# my-hello-world.net
KiCad netlist of a schematic drawn in EAGLE
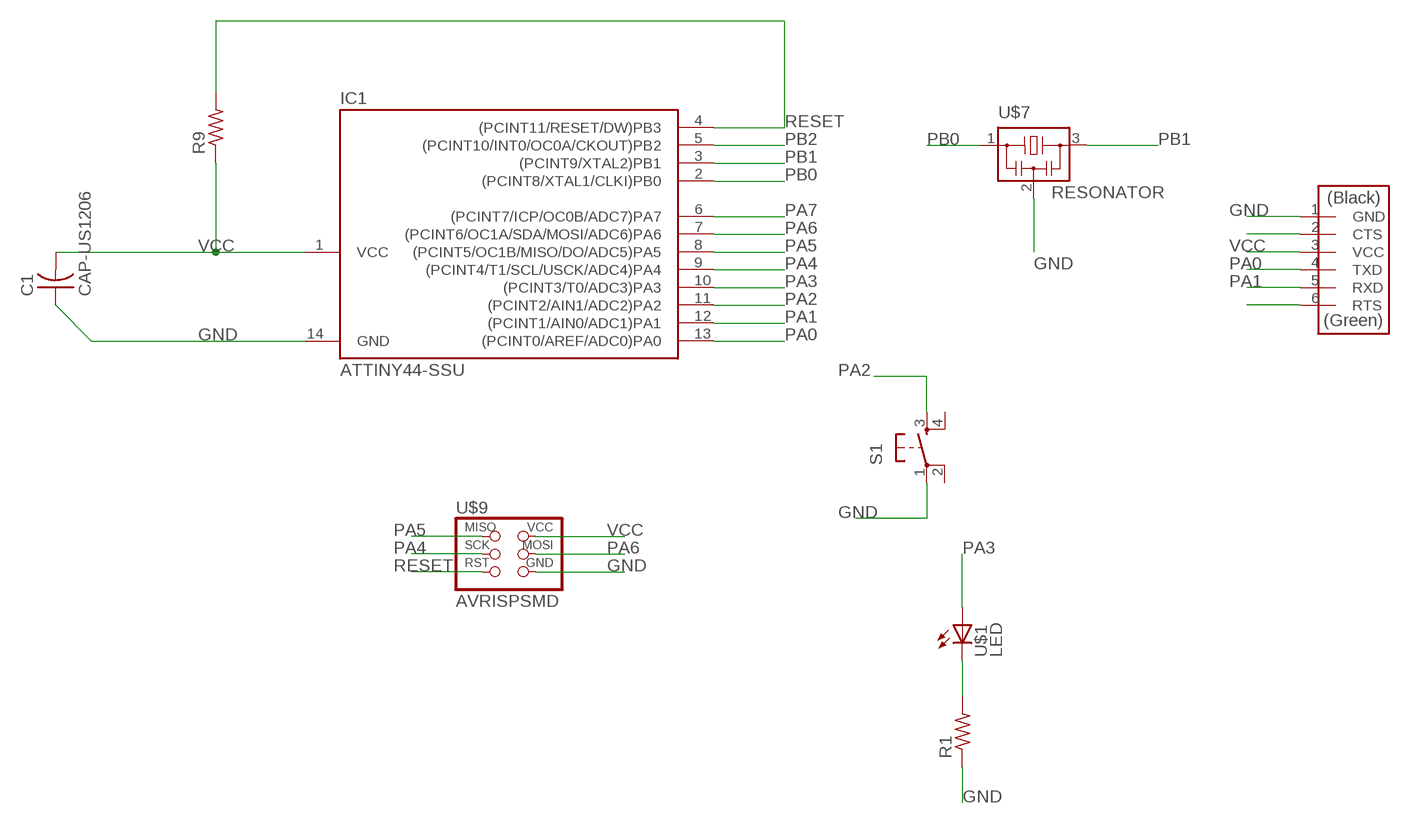
[diagram p0: schematic, sheet 1]

(export (version "E")
  (design (tool "Eeschema 10.0.6"))
  (components
    (comp (ref "C1")
      (value "CAP-US1206")
      (footprint "eagle-import:C1206")
      (libsource (lib "eagle-import") (part "CAP-US1206"))
    )
    (comp (ref "IC1")
      (value "ATTINY44-SSU")
      (footprint "eagle-import:SOIC14")
      (libsource (lib "eagle-import") (part "ATTINY44-SSU"))
    )
    (comp (ref "R1")
      (value "RES-US1206")
      (footprint "eagle-import:R1206")
      (libsource (lib "eagle-import") (part "RES-US1206"))
    )
    (comp (ref "R9")
      (value "RES-US1206")
      (footprint "eagle-import:R1206")
      (libsource (lib "eagle-import") (part "RES-US1206"))
    )
    (comp (ref "S1")
      (value "6MM_SWITCH6MM_SWITCH")
      (footprint "eagle-import:6MM_SWITCH")
      (libsource (lib "eagle-import") (part "6MM_SWITCH6MM_SWITCH"))
    )
    (comp (ref "U$1")
      (value "LED")
      (footprint "eagle-import:LED1206")
      (libsource (lib "eagle-import") (part "LED"))
    )
    (comp (ref "U$7")
      (value "RESONATOR")
      (footprint "eagle-import:EFOBM")
      (libsource (lib "eagle-import") (part "RESONATOR"))
    )
    (comp (ref "U$9")
      (value "AVRISPSMD")
      (footprint "eagle-import:2X03SMD")
      (libsource (lib "eagle-import") (part "AVRISPSMD"))
    )
    (comp (ref "U$10")
      (value "FTDI-SMD-HEADER")
      (footprint "eagle-import:1X06SMD")
      (libsource (lib "eagle-import") (part "FTDI-SMD-HEADER"))
    )
  )
  (nets
    (net (code "1") (name "/GND") (class "Default")
      (node (ref "C1") (pin "1") (pinfunction "1_1") (pintype "passive"))
      (node (ref "IC1") (pin "14") (pinfunction "GND_14") (pintype "power_in"))
      (node (ref "R1") (pin "1") (pinfunction "1_1") (pintype "passive"))
      (node (ref "S1") (pin "1") (pinfunction "P_1") (pintype "passive"))
      (node (ref "U$10") (pin "1") (pinfunction "GND_1") (pintype "bidirectional"))
      (node (ref "U$7") (pin "2") (pinfunction "2_2") (pintype "passive"))
      (node (ref "U$9") (pin "6") (pinfunction "GND_6") (pintype "passive"))
    )
    (net (code "2") (name "/PA0") (class "Default")
      (node (ref "IC1") (pin "13") (pinfunction "(PCINT0/AREF/ADC0)PA0_13") (pintype "bidirectional"))
      (node (ref "U$10") (pin "4") (pinfunction "TXD_4") (pintype "bidirectional"))
    )
    (net (code "3") (name "/PA1") (class "Default")
      (node (ref "IC1") (pin "12") (pinfunction "(PCINT1/AIN0/ADC1)PA1_12") (pintype "bidirectional"))
      (node (ref "U$10") (pin "5") (pinfunction "RXD_5") (pintype "bidirectional"))
    )
    (net (code "4") (name "/PA2") (class "Default")
      (node (ref "IC1") (pin "11") (pinfunction "(PCINT2/AIN1/ADC2)PA2_11") (pintype "bidirectional"))
      (node (ref "S1") (pin "3") (pinfunction "S_3") (pintype "passive"))
    )
    (net (code "5") (name "/PA3") (class "Default")
      (node (ref "IC1") (pin "10") (pinfunction "(PCINT3/T0/ADC3)PA3_10") (pintype "bidirectional"))
      (node (ref "U$1") (pin "1") (pinfunction "A_1") (pintype "passive"))
    )
    (net (code "6") (name "/PA4") (class "Default")
      (node (ref "IC1") (pin "9") (pinfunction "(PCINT4/T1/SCL/USCK/ADC4)PA4_9") (pintype "bidirectional"))
      (node (ref "U$9") (pin "3") (pinfunction "SCK_3") (pintype "passive"))
    )
    (net (code "7") (name "/PA5") (class "Default")
      (node (ref "IC1") (pin "8") (pinfunction "(PCINT5/OC1B/MISO/DO/ADC5)PA5_8") (pintype "bidirectional"))
      (node (ref "U$9") (pin "1") (pinfunction "MISO_1") (pintype "passive"))
    )
    (net (code "8") (name "/PA6") (class "Default")
      (node (ref "IC1") (pin "7") (pinfunction "(PCINT6/OC1A/SDA/MOSI/ADC6)PA6_7") (pintype "bidirectional"))
      (node (ref "U$9") (pin "4") (pinfunction "MOSI_4") (pintype "passive"))
    )
    (net (code "9") (name "/PA7") (class "Default")
      (node (ref "IC1") (pin "6") (pinfunction "(PCINT7/ICP/OC0B/ADC7)PA7_6") (pintype "bidirectional"))
    )
    (net (code "10") (name "/PB0") (class "Default")
      (node (ref "IC1") (pin "2") (pinfunction "(PCINT8/XTAL1/CLKI)PB0_2") (pintype "bidirectional"))
      (node (ref "U$7") (pin "1") (pinfunction "1_1") (pintype "passive"))
    )
    (net (code "11") (name "/PB1") (class "Default")
      (node (ref "IC1") (pin "3") (pinfunction "(PCINT9/XTAL2)PB1_3") (pintype "bidirectional"))
      (node (ref "U$7") (pin "3") (pinfunction "3_3") (pintype "passive"))
    )
    (net (code "12") (name "/PB2") (class "Default")
      (node (ref "IC1") (pin "5") (pinfunction "(PCINT10/INT0/OC0A/CKOUT)PB2_5") (pintype "bidirectional"))
    )
    (net (code "13") (name "/RESET") (class "Default")
      (node (ref "IC1") (pin "4") (pinfunction "(PCINT11/RESET/DW)PB3_4") (pintype "bidirectional"))
      (node (ref "R9") (pin "2") (pinfunction "2_2") (pintype "passive"))
      (node (ref "U$9") (pin "5") (pinfunction "RST_5") (pintype "passive"))
    )
    (net (code "14") (name "/VCC") (class "Default")
      (node (ref "C1") (pin "2") (pinfunction "2_2") (pintype "passive"))
      (node (ref "IC1") (pin "1") (pinfunction "VCC_1") (pintype "power_in"))
      (node (ref "R9") (pin "1") (pinfunction "1_1") (pintype "passive"))
      (node (ref "U$10") (pin "3") (pinfunction "VCC_3") (pintype "bidirectional"))
      (node (ref "U$9") (pin "2") (pinfunction "VCC_2") (pintype "passive"))
    )
    (net (code "15") (name "Net-(U$1-C)") (class "Default")
      (node (ref "R1") (pin "2") (pinfunction "2_2") (pintype "passive"))
      (node (ref "U$1") (pin "2") (pinfunction "C_2") (pintype "passive"))
    )
    (net (code "16") (name "unconnected-(S1-P1-Pad2)") (class "Default")
      (node (ref "S1") (pin "2") (pinfunction "P1_2") (pintype "passive"))
    )
    (net (code "17") (name "unconnected-(S1-S1-Pad4)") (class "Default")
      (node (ref "S1") (pin "4") (pinfunction "S1_4") (pintype "passive"))
    )
    (net (code "18") (name "unconnected-(U$10-CTS-Pad2)") (class "Default")
      (node (ref "U$10") (pin "2") (pinfunction "CTS_2") (pintype "bidirectional"))
    )
    (net (code "19") (name "unconnected-(U$10-RTS-Pad6)") (class "Default")
      (node (ref "U$10") (pin "6") (pinfunction "RTS_6") (pintype "bidirectional"))
    )
  )
)
